# main.net
KiCad netlist of a schematic drawn in EAGLE
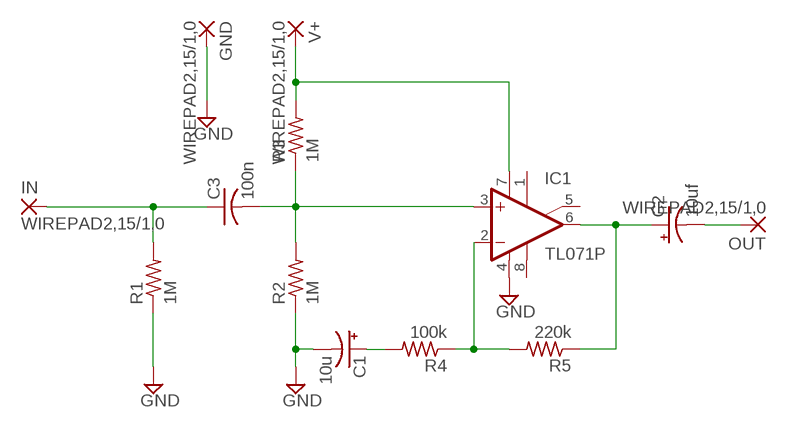
[diagram p0: schematic, sheet 1]

(export (version "E")
  (design (tool "Eeschema 10.0.6"))
  (components
    (comp (ref "C1")
      (value "10u")
      (footprint "eagle-import:PANASONIC_C")
      (libsource (lib "eagle-import") (part "CPOL-USC"))
    )
    (comp (ref "C2")
      (value "10uf")
      (footprint "eagle-import:PANASONIC_C")
      (libsource (lib "eagle-import") (part "CPOL-USC"))
    )
    (comp (ref "C3")
      (value "100n")
      (footprint "eagle-import:C0805")
      (libsource (lib "eagle-import") (part "C-USC0805"))
    )
    (comp (ref "GND")
      (value "WIREPAD2,15/1,0")
      (footprint "eagle-import:2,15_1,0")
      (libsource (lib "eagle-import") (part "WIREPAD2,15/1,0"))
    )
    (comp (ref "IC1")
      (value "TL071P")
      (footprint "eagle-import:DIL08")
      (libsource (lib "eagle-import") (part "TL071P"))
    )
    (comp (ref "IN")
      (value "WIREPAD2,15/1,0")
      (footprint "eagle-import:2,15_1,0")
      (libsource (lib "eagle-import") (part "WIREPAD2,15/1,0"))
    )
    (comp (ref "OUT")
      (value "WIREPAD2,15/1,0")
      (footprint "eagle-import:2,15_1,0")
      (libsource (lib "eagle-import") (part "WIREPAD2,15/1,0"))
    )
    (comp (ref "R1")
      (value "1M")
      (footprint "eagle-import:R0805")
      (libsource (lib "eagle-import") (part "R-US_R0805"))
    )
    (comp (ref "R2")
      (value "1M")
      (footprint "eagle-import:R0805")
      (libsource (lib "eagle-import") (part "R-US_R0805"))
    )
    (comp (ref "R3")
      (value "1M")
      (footprint "eagle-import:R0805")
      (libsource (lib "eagle-import") (part "R-US_R0805"))
    )
    (comp (ref "R4")
      (value "100k")
      (footprint "eagle-import:R0805")
      (libsource (lib "eagle-import") (part "R-US_R0805"))
    )
    (comp (ref "R5")
      (value "220k")
      (footprint "eagle-import:R0805")
      (libsource (lib "eagle-import") (part "R-US_R0805"))
    )
    (comp (ref "V+")
      (value "WIREPAD2,15/1,0")
      (footprint "eagle-import:2,15_1,0")
      (libsource (lib "eagle-import") (part "WIREPAD2,15/1,0"))
    )
  )
  (nets
    (net (code "1") (name "GND") (class "Default")
      (node (ref "C1") (pin "-") (pinfunction "-_-") (pintype "passive"))
      (node (ref "GND") (pin "1") (pinfunction "P_1") (pintype "passive"))
      (node (ref "IC1") (pin "4") (pinfunction "V-_4") (pintype "power_in"))
      (node (ref "R1") (pin "1") (pinfunction "1_1") (pintype "passive"))
      (node (ref "R2") (pin "1") (pinfunction "1_1") (pintype "passive"))
    )
    (net (code "2") (name "Net-(C1-Pad+)") (class "Default")
      (node (ref "C1") (pin "+") (pinfunction "+_+") (pintype "passive"))
      (node (ref "R4") (pin "2") (pinfunction "2_2") (pintype "passive"))
    )
    (net (code "3") (name "Net-(IC1-+IN)") (class "Default")
      (node (ref "C3") (pin "2") (pinfunction "2_2") (pintype "passive"))
      (node (ref "IC1") (pin "3") (pinfunction "+IN_3") (pintype "input"))
      (node (ref "R2") (pin "2") (pinfunction "2_2") (pintype "passive"))
      (node (ref "R3") (pin "1") (pinfunction "1_1") (pintype "passive"))
    )
    (net (code "4") (name "Net-(IC1--IN)") (class "Default")
      (node (ref "IC1") (pin "2") (pinfunction "-IN_2") (pintype "input"))
      (node (ref "R4") (pin "1") (pinfunction "1_1") (pintype "passive"))
      (node (ref "R5") (pin "2") (pinfunction "2_2") (pintype "passive"))
    )
    (net (code "5") (name "Net-(IC1-OUT)") (class "Default")
      (node (ref "C2") (pin "+") (pinfunction "+_+") (pintype "passive"))
      (node (ref "IC1") (pin "6") (pinfunction "OUT_6") (pintype "output"))
      (node (ref "R5") (pin "1") (pinfunction "1_1") (pintype "passive"))
    )
    (net (code "6") (name "Net-(IC1-V+)") (class "Default")
      (node (ref "IC1") (pin "7") (pinfunction "V+_7") (pintype "power_in"))
      (node (ref "R3") (pin "2") (pinfunction "2_2") (pintype "passive"))
      (node (ref "V+") (pin "1") (pinfunction "P_1") (pintype "passive"))
    )
    (net (code "7") (name "Net-(IN-P)") (class "Default")
      (node (ref "C3") (pin "1") (pinfunction "1_1") (pintype "passive"))
      (node (ref "IN") (pin "1") (pinfunction "P_1") (pintype "passive"))
      (node (ref "R1") (pin "2") (pinfunction "2_2") (pintype "passive"))
    )
    (net (code "8") (name "Net-(OUT-P)") (class "Default")
      (node (ref "C2") (pin "-") (pinfunction "-_-") (pintype "passive"))
      (node (ref "OUT") (pin "1") (pinfunction "P_1") (pintype "passive"))
    )
    (net (code "9") (name "unconnected-(IC1-ON1-Pad1)") (class "Default")
      (node (ref "IC1") (pin "1") (pinfunction "ON1_1") (pintype "passive"))
    )
    (net (code "10") (name "unconnected-(IC1-ON2-Pad5)") (class "Default")
      (node (ref "IC1") (pin "5") (pinfunction "ON2_5") (pintype "passive"))
    )
    (net (code "11") (name "unconnected-(IC1-OPT-Pad8)") (class "Default")
      (node (ref "IC1") (pin "8") (pinfunction "OPT_8") (pintype "passive"))
    )
  )
)
